# G11_CG_for_G8.net
KiCad netlist of a schematic drawn in EAGLE
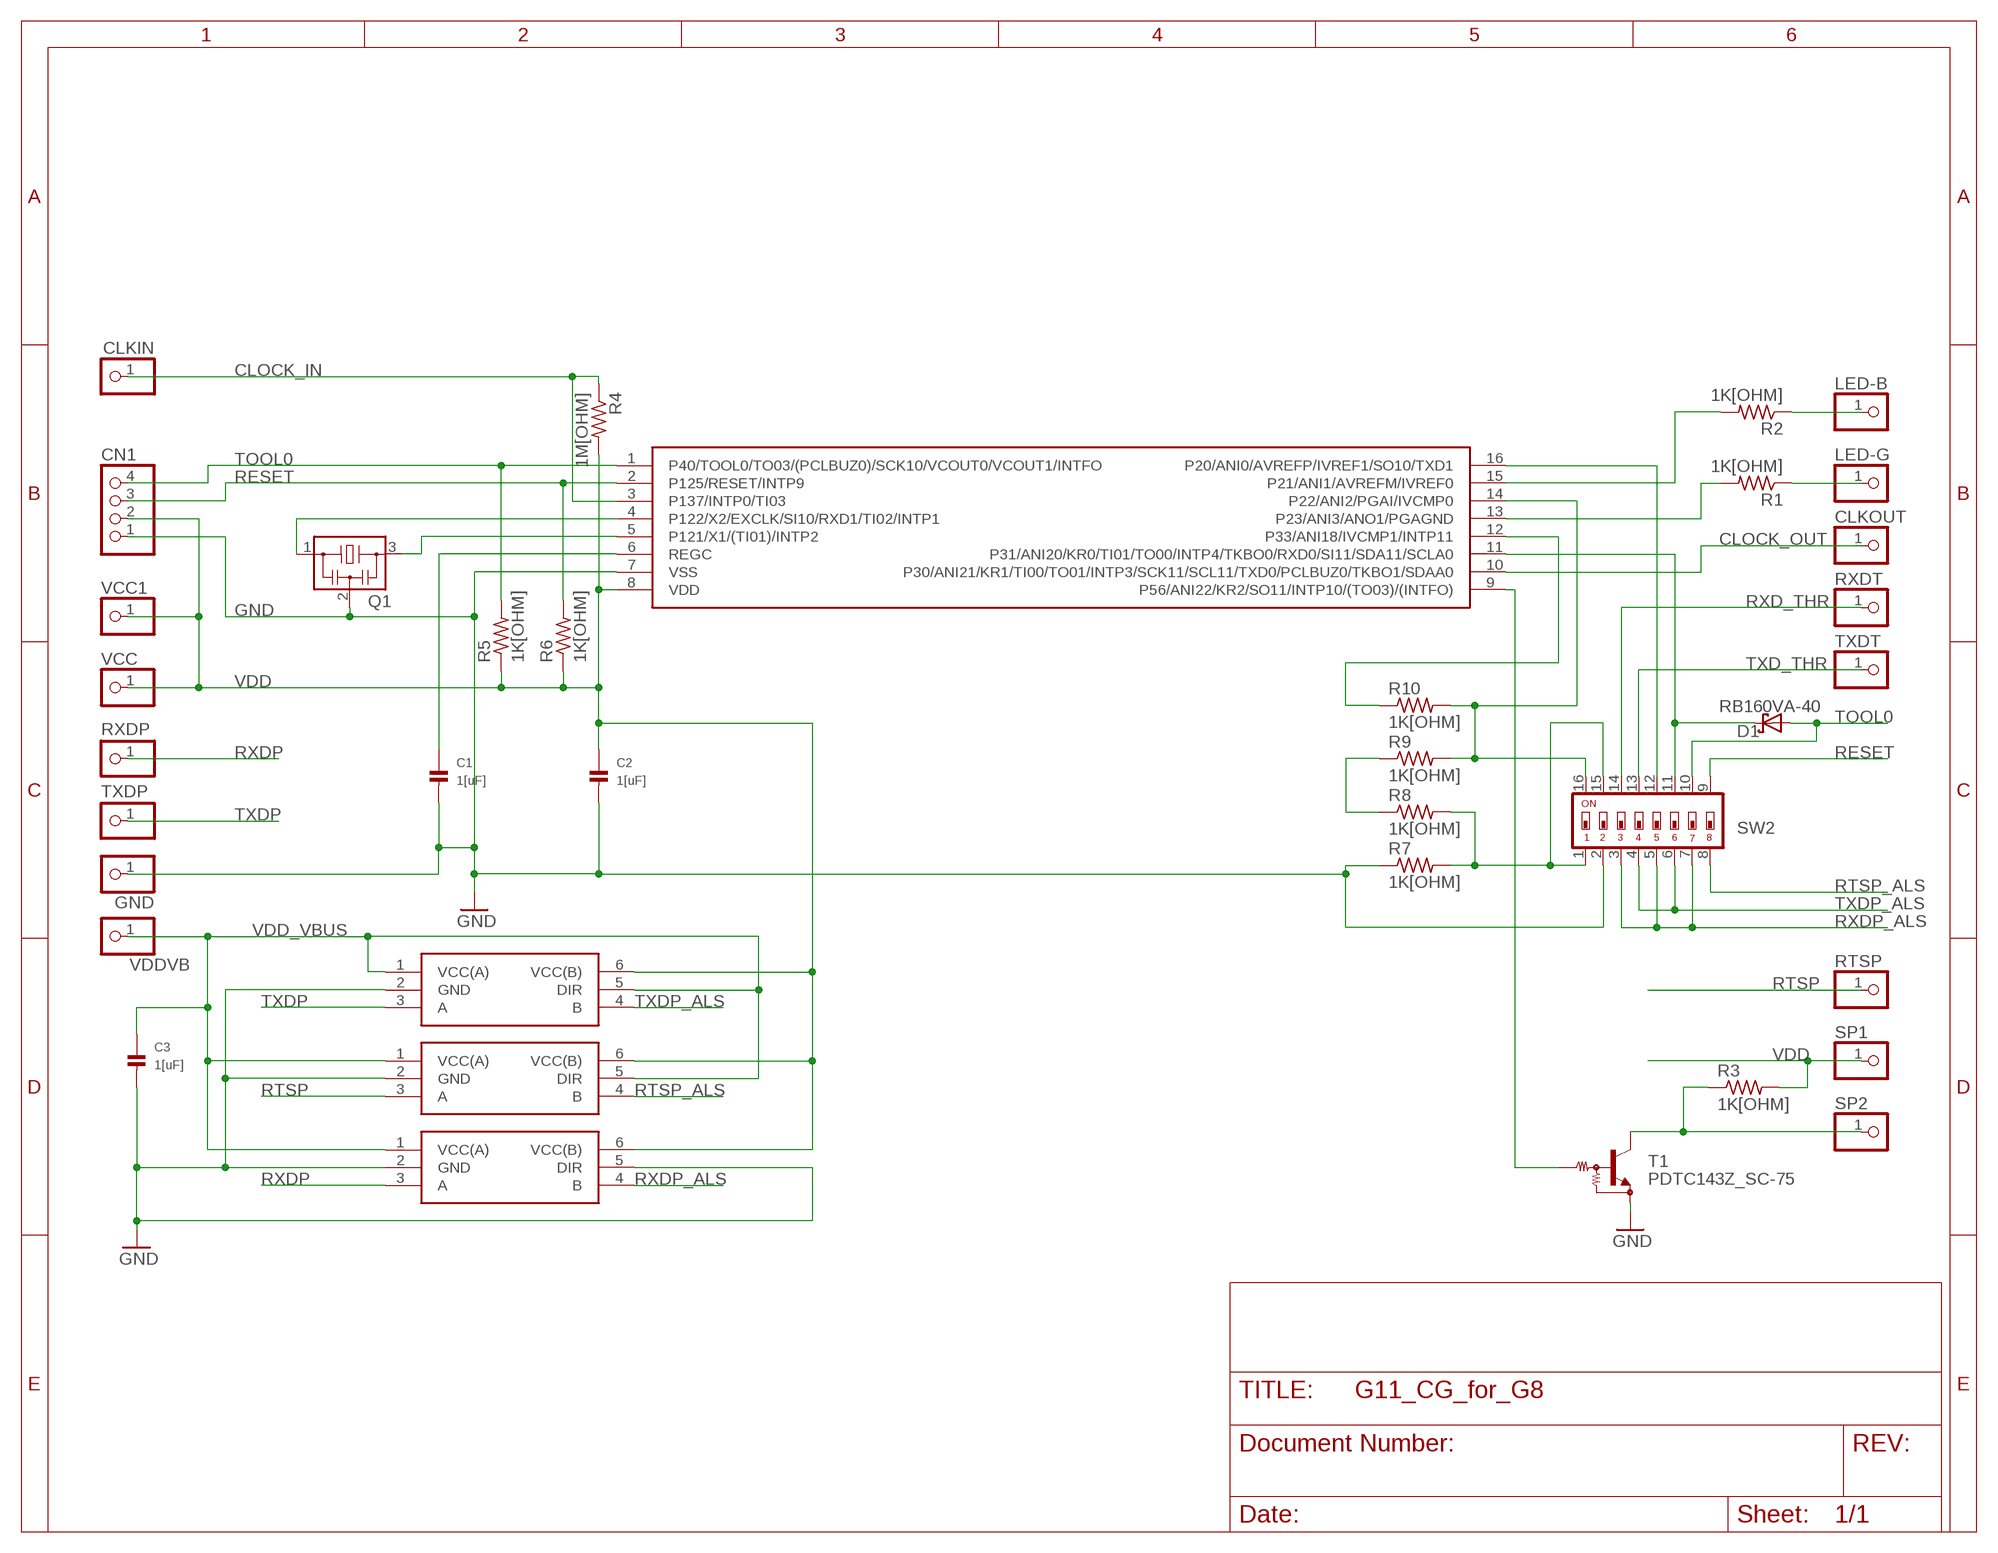
[diagram p0: schematic, sheet 1]

(export (version "E")
  (design (tool "Eeschema 10.0.6"))
  (components
    (comp (ref "C1")
      (value "1[uF]")
      (footprint "eagle-import:_0603")
      (libsource (lib "eagle-import") (part "CAP_CERAMIC_0603"))
    )
    (comp (ref "C2")
      (value "1[uF]")
      (footprint "eagle-import:_0603")
      (libsource (lib "eagle-import") (part "CAP_CERAMIC_0603"))
    )
    (comp (ref "C3")
      (value "1[uF]")
      (footprint "eagle-import:_0603")
      (libsource (lib "eagle-import") (part "CAP_CERAMIC_0603"))
    )
    (comp (ref "CLKIN")
      (value "PINHD-1X1")
      (footprint "eagle-import:1X01")
      (libsource (lib "eagle-import") (part "PINHD-1X1"))
    )
    (comp (ref "CLKOUT")
      (value "PINHD-1X1")
      (footprint "eagle-import:1X01")
      (libsource (lib "eagle-import") (part "PINHD-1X1"))
    )
    (comp (ref "CN1")
      (value "PINHD-1X4")
      (footprint "eagle-import:1X04")
      (libsource (lib "eagle-import") (part "PINHD-1X4"))
    )
    (comp (ref "D1")
      (value "RB160VA-40")
      (footprint "eagle-import:TUMD2")
      (libsource (lib "eagle-import") (part "RB160VA-40"))
    )
    (comp (ref "GND")
      (value "PINHD-1X1")
      (footprint "eagle-import:1X01")
      (libsource (lib "eagle-import") (part "PINHD-1X1"))
    )
    (comp (ref "LED-B")
      (value "PINHD-1X1")
      (footprint "eagle-import:1X01")
      (libsource (lib "eagle-import") (part "PINHD-1X1"))
    )
    (comp (ref "LED-G")
      (value "PINHD-1X1")
      (footprint "eagle-import:1X01")
      (libsource (lib "eagle-import") (part "PINHD-1X1"))
    )
    (comp (ref "Q1")
      (value "CSTNE")
      (footprint "eagle-import:CSTNE")
      (libsource (lib "eagle-import") (part "CSTNE"))
    )
    (comp (ref "R1")
      (value "1K[OHM]")
      (footprint "eagle-import:R0603")
      (libsource (lib "eagle-import") (part "R-US_R0603"))
    )
    (comp (ref "R2")
      (value "1K[OHM]")
      (footprint "eagle-import:R0603")
      (libsource (lib "eagle-import") (part "R-US_R0603"))
    )
    (comp (ref "R3")
      (value "1K[OHM]")
      (footprint "eagle-import:R0603")
      (libsource (lib "eagle-import") (part "R-US_R0603"))
    )
    (comp (ref "R4")
      (value "1M[OHM]")
      (footprint "eagle-import:R0603")
      (libsource (lib "eagle-import") (part "R-US_R0603"))
    )
    (comp (ref "R5")
      (value "1K[OHM]")
      (footprint "eagle-import:R0603")
      (libsource (lib "eagle-import") (part "R-US_R0603"))
    )
    (comp (ref "R6")
      (value "1K[OHM]")
      (footprint "eagle-import:R0603")
      (libsource (lib "eagle-import") (part "R-US_R0603"))
    )
    (comp (ref "R7")
      (value "1K[OHM]")
      (footprint "eagle-import:R0603")
      (libsource (lib "eagle-import") (part "R-US_R0603"))
    )
    (comp (ref "R8")
      (value "1K[OHM]")
      (footprint "eagle-import:R0603")
      (libsource (lib "eagle-import") (part "R-US_R0603"))
    )
    (comp (ref "R9")
      (value "1K[OHM]")
      (footprint "eagle-import:R0603")
      (libsource (lib "eagle-import") (part "R-US_R0603"))
    )
    (comp (ref "R10")
      (value "1K[OHM]")
      (footprint "eagle-import:R0603")
      (libsource (lib "eagle-import") (part "R-US_R0603"))
    )
    (comp (ref "RTSP")
      (value "PINHD-1X1")
      (footprint "eagle-import:1X01")
      (libsource (lib "eagle-import") (part "PINHD-1X1"))
    )
    (comp (ref "RXDP")
      (value "PINHD-1X1")
      (footprint "eagle-import:1X01")
      (libsource (lib "eagle-import") (part "PINHD-1X1"))
    )
    (comp (ref "RXDT")
      (value "PINHD-1X1")
      (footprint "eagle-import:1X01")
      (libsource (lib "eagle-import") (part "PINHD-1X1"))
    )
    (comp (ref "SP1")
      (value "PINHD-1X1")
      (footprint "eagle-import:1X01")
      (libsource (lib "eagle-import") (part "PINHD-1X1"))
    )
    (comp (ref "SP2")
      (value "PINHD-1X1")
      (footprint "eagle-import:1X01")
      (libsource (lib "eagle-import") (part "PINHD-1X1"))
    )
    (comp (ref "SW2")
      (value "SWS008")
      (footprint "eagle-import:SMS-008")
      (libsource (lib "eagle-import") (part "SWS008"))
    )
    (comp (ref "T1")
      (value "PDTC143Z_SC-75")
      (footprint "eagle-import:SC-75")
      (libsource (lib "eagle-import") (part "DTC1XXXZPDTC143Z"))
    )
    (comp (ref "TXDP")
      (value "PINHD-1X1")
      (footprint "eagle-import:1X01")
      (libsource (lib "eagle-import") (part "PINHD-1X1"))
    )
    (comp (ref "TXDT")
      (value "PINHD-1X1")
      (footprint "eagle-import:1X01")
      (libsource (lib "eagle-import") (part "PINHD-1X1"))
    )
    (comp (ref "U1")
      (value "RL78/G11_SSOP16")
      (footprint "eagle-import:SSOP16_(4.4X5.0)")
      (libsource (lib "eagle-import") (part "RL78/G11_SSOP16"))
    )
    (comp (ref "U2")
      (value "74LVC1T45W6")
      (footprint "eagle-import:SOT-26")
      (libsource (lib "eagle-import") (part "74LVC1T45W6"))
    )
    (comp (ref "U3")
      (value "74LVC1T45W6")
      (footprint "eagle-import:SOT-26")
      (libsource (lib "eagle-import") (part "74LVC1T45W6"))
    )
    (comp (ref "U4")
      (value "74LVC1T45W6")
      (footprint "eagle-import:SOT-26")
      (libsource (lib "eagle-import") (part "74LVC1T45W6"))
    )
    (comp (ref "VCC")
      (value "PINHD-1X1")
      (footprint "eagle-import:1X01")
      (libsource (lib "eagle-import") (part "PINHD-1X1"))
    )
    (comp (ref "VCC1")
      (value "PINHD-1X1")
      (footprint "eagle-import:1X01")
      (libsource (lib "eagle-import") (part "PINHD-1X1"))
    )
    (comp (ref "VDDVB")
      (value "PINHD-1X1")
      (footprint "eagle-import:1X01")
      (libsource (lib "eagle-import") (part "PINHD-1X1"))
    )
  )
  (nets
    (net (code "1") (name "/CLOCK_IN") (class "Default")
      (node (ref "CLKIN") (pin "1") (pinfunction "1_1") (pintype "passive"))
      (node (ref "R4") (pin "1") (pinfunction "1_1") (pintype "passive"))
      (node (ref "U1") (pin "3") (pinfunction "P137/INTP0/TI03_3") (pintype "bidirectional"))
    )
    (net (code "2") (name "/CLOCK_OUT") (class "Default")
      (node (ref "CLKOUT") (pin "1") (pinfunction "1_1") (pintype "passive"))
      (node (ref "U1") (pin "10") (pinfunction "P30/ANI21/KR1/TI00/TO01/INTP3/SCK11/SCL11/TXD0/PCLBUZ0/TKBO1/SDAA0_10") (pintype "bidirectional"))
    )
    (net (code "3") (name "/RESET") (class "Default")
      (node (ref "CN1") (pin "3") (pinfunction "3_3") (pintype "passive"))
      (node (ref "R6") (pin "2") (pinfunction "2_2") (pintype "passive"))
      (node (ref "SW2") (pin "9") (pinfunction "9_9") (pintype "passive"))
      (node (ref "U1") (pin "2") (pinfunction "P125/RESET/INTP9_2") (pintype "bidirectional"))
    )
    (net (code "4") (name "/RTSP") (class "Default")
      (node (ref "RTSP") (pin "1") (pinfunction "1_1") (pintype "passive"))
      (node (ref "U3") (pin "3") (pinfunction "A_3") (pintype "bidirectional"))
    )
    (net (code "5") (name "/RTSP_ALS") (class "Default")
      (node (ref "SW2") (pin "8") (pinfunction "8_8") (pintype "passive"))
      (node (ref "U3") (pin "4") (pinfunction "B_4") (pintype "bidirectional"))
    )
    (net (code "6") (name "/RXDP") (class "Default")
      (node (ref "RXDP") (pin "1") (pinfunction "1_1") (pintype "passive"))
      (node (ref "U4") (pin "3") (pinfunction "A_3") (pintype "bidirectional"))
    )
    (net (code "7") (name "/RXDP_ALS") (class "Default")
      (node (ref "SW2") (pin "3") (pinfunction "3_3") (pintype "passive"))
      (node (ref "SW2") (pin "5") (pinfunction "5_5") (pintype "passive"))
      (node (ref "SW2") (pin "7") (pinfunction "7_7") (pintype "passive"))
      (node (ref "U4") (pin "4") (pinfunction "B_4") (pintype "bidirectional"))
    )
    (net (code "8") (name "/RXD_THR") (class "Default")
      (node (ref "RXDT") (pin "1") (pinfunction "1_1") (pintype "passive"))
      (node (ref "SW2") (pin "14") (pinfunction "14_14") (pintype "passive"))
    )
    (net (code "9") (name "/TOOL0") (class "Default")
      (node (ref "CN1") (pin "4") (pinfunction "4_4") (pintype "passive"))
      (node (ref "D1") (pin "P$2") (pinfunction "A_P$2") (pintype "passive"))
      (node (ref "R5") (pin "2") (pinfunction "2_2") (pintype "passive"))
      (node (ref "SW2") (pin "10") (pinfunction "10_10") (pintype "passive"))
      (node (ref "U1") (pin "1") (pinfunction "P40/TOOL0/TO03/(PCLBUZ0)/SCK10/VCOUT0/VCOUT1/INTFO_1") (pintype "bidirectional"))
    )
    (net (code "10") (name "/TXDP") (class "Default")
      (node (ref "TXDP") (pin "1") (pinfunction "1_1") (pintype "passive"))
      (node (ref "U2") (pin "3") (pinfunction "A_3") (pintype "bidirectional"))
    )
    (net (code "11") (name "/TXDP_ALS") (class "Default")
      (node (ref "SW2") (pin "4") (pinfunction "4_4") (pintype "passive"))
      (node (ref "SW2") (pin "6") (pinfunction "6_6") (pintype "passive"))
      (node (ref "U2") (pin "4") (pinfunction "B_4") (pintype "bidirectional"))
    )
    (net (code "12") (name "/TXD_THR") (class "Default")
      (node (ref "SW2") (pin "13") (pinfunction "13_13") (pintype "passive"))
      (node (ref "TXDT") (pin "1") (pinfunction "1_1") (pintype "passive"))
    )
    (net (code "13") (name "/VDD") (class "Default")
      (node (ref "C2") (pin "1") (pinfunction "P$1_1") (pintype "passive"))
      (node (ref "CN1") (pin "2") (pinfunction "2_2") (pintype "passive"))
      (node (ref "R3") (pin "2") (pinfunction "2_2") (pintype "passive"))
      (node (ref "R4") (pin "2") (pinfunction "2_2") (pintype "passive"))
      (node (ref "R5") (pin "1") (pinfunction "1_1") (pintype "passive"))
      (node (ref "R6") (pin "1") (pinfunction "1_1") (pintype "passive"))
      (node (ref "SP1") (pin "1") (pinfunction "1_1") (pintype "passive"))
      (node (ref "U1") (pin "8") (pinfunction "VDD_8") (pintype "power_in"))
      (node (ref "U2") (pin "6") (pinfunction "VCC(B)_6") (pintype "power_in"))
      (node (ref "U3") (pin "6") (pinfunction "VCC(B)_6") (pintype "power_in"))
      (node (ref "U4") (pin "6") (pinfunction "VCC(B)_6") (pintype "power_in"))
      (node (ref "VCC") (pin "1") (pinfunction "1_1") (pintype "passive"))
      (node (ref "VCC1") (pin "1") (pinfunction "1_1") (pintype "passive"))
    )
    (net (code "14") (name "/VDD_VBUS") (class "Default")
      (node (ref "C3") (pin "1") (pinfunction "P$1_1") (pintype "passive"))
      (node (ref "U2") (pin "1") (pinfunction "VCC(A)_1") (pintype "power_in"))
      (node (ref "U2") (pin "5") (pinfunction "DIR_5") (pintype "input"))
      (node (ref "U3") (pin "1") (pinfunction "VCC(A)_1") (pintype "power_in"))
      (node (ref "U3") (pin "5") (pinfunction "DIR_5") (pintype "input"))
      (node (ref "U4") (pin "1") (pinfunction "VCC(A)_1") (pintype "power_in"))
      (node (ref "VDDVB") (pin "1") (pinfunction "1_1") (pintype "passive"))
    )
    (net (code "15") (name "GND") (class "Default")
      (node (ref "C1") (pin "2") (pinfunction "P$2_2") (pintype "passive"))
      (node (ref "C2") (pin "2") (pinfunction "P$2_2") (pintype "passive"))
      (node (ref "C3") (pin "2") (pinfunction "P$2_2") (pintype "passive"))
      (node (ref "CN1") (pin "1") (pinfunction "1_1") (pintype "passive"))
      (node (ref "GND") (pin "1") (pinfunction "1_1") (pintype "passive"))
      (node (ref "Q1") (pin "2") (pinfunction "2_2") (pintype "passive"))
      (node (ref "R7") (pin "1") (pinfunction "1_1") (pintype "passive"))
      (node (ref "SW2") (pin "2") (pinfunction "2_2") (pintype "passive"))
      (node (ref "T1") (pin "2") (pinfunction "E_2") (pintype "passive"))
      (node (ref "U1") (pin "7") (pinfunction "VSS_7") (pintype "power_in"))
      (node (ref "U2") (pin "2") (pinfunction "GND_2") (pintype "power_in"))
      (node (ref "U3") (pin "2") (pinfunction "GND_2") (pintype "power_in"))
      (node (ref "U4") (pin "2") (pinfunction "GND_2") (pintype "power_in"))
      (node (ref "U4") (pin "5") (pinfunction "DIR_5") (pintype "input"))
    )
    (net (code "16") (name "Net-(C1-P$1)") (class "Default")
      (node (ref "C1") (pin "1") (pinfunction "P$1_1") (pintype "passive"))
      (node (ref "U1") (pin "6") (pinfunction "REGC_6") (pintype "bidirectional"))
    )
    (net (code "17") (name "Net-(D1-C)") (class "Default")
      (node (ref "D1") (pin "P$1") (pinfunction "C_P$1") (pintype "passive"))
      (node (ref "SW2") (pin "11") (pinfunction "11_11") (pintype "passive"))
      (node (ref "U1") (pin "11") (pinfunction "P31/ANI20/KR0/TI01/TO00/INTP4/TKBO0/RXD0/SI11/SDA11/SCLA0_11") (pintype "bidirectional"))
    )
    (net (code "18") (name "Net-(LED-B-Pad1)") (class "Default")
      (node (ref "LED-B") (pin "1") (pinfunction "1_1") (pintype "passive"))
      (node (ref "R2") (pin "1") (pinfunction "1_1") (pintype "passive"))
    )
    (net (code "19") (name "Net-(LED-G-Pad1)") (class "Default")
      (node (ref "LED-G") (pin "1") (pinfunction "1_1") (pintype "passive"))
      (node (ref "R1") (pin "1") (pinfunction "1_1") (pintype "passive"))
    )
    (net (code "20") (name "Net-(R7-Pad2)") (class "Default")
      (node (ref "R7") (pin "2") (pinfunction "2_2") (pintype "passive"))
      (node (ref "R8") (pin "2") (pinfunction "2_2") (pintype "passive"))
      (node (ref "SW2") (pin "1") (pinfunction "1_1") (pintype "passive"))
      (node (ref "SW2") (pin "15") (pinfunction "15_15") (pintype "passive"))
    )
    (net (code "21") (name "Net-(R8-Pad1)") (class "Default")
      (node (ref "R8") (pin "1") (pinfunction "1_1") (pintype "passive"))
      (node (ref "R9") (pin "1") (pinfunction "1_1") (pintype "passive"))
    )
    (net (code "22") (name "Net-(T1-B)") (class "Default")
      (node (ref "T1") (pin "1") (pinfunction "B_1") (pintype "passive"))
      (node (ref "U1") (pin "9") (pinfunction "P56/ANI22/KR2/SO11/INTP10/(TO03)/(INTFO)_9") (pintype "bidirectional"))
    )
    (net (code "23") (name "Net-(T1-C)") (class "Default")
      (node (ref "R3") (pin "1") (pinfunction "1_1") (pintype "passive"))
      (node (ref "SP2") (pin "1") (pinfunction "1_1") (pintype "passive"))
      (node (ref "T1") (pin "3") (pinfunction "C_3") (pintype "passive"))
    )
    (net (code "24") (name "Net-(U1-P20{slash}ANI0{slash}AVREFP{slash}IVREF1{slash}SO10{slash}TXD1)") (class "Default")
      (node (ref "SW2") (pin "12") (pinfunction "12_12") (pintype "passive"))
      (node (ref "U1") (pin "16") (pinfunction "P20/ANI0/AVREFP/IVREF1/SO10/TXD1_16") (pintype "bidirectional"))
    )
    (net (code "25") (name "Net-(U1-P21{slash}ANI1{slash}AVREFM{slash}IVREF0)") (class "Default")
      (node (ref "R2") (pin "2") (pinfunction "2_2") (pintype "passive"))
      (node (ref "U1") (pin "15") (pinfunction "P21/ANI1/AVREFM/IVREF0_15") (pintype "bidirectional"))
    )
    (net (code "26") (name "Net-(U1-P22{slash}ANI2{slash}PGAI{slash}IVCMP0)") (class "Default")
      (node (ref "R10") (pin "2") (pinfunction "2_2") (pintype "passive"))
      (node (ref "R9") (pin "2") (pinfunction "2_2") (pintype "passive"))
      (node (ref "SW2") (pin "16") (pinfunction "16_16") (pintype "passive"))
      (node (ref "U1") (pin "14") (pinfunction "P22/ANI2/PGAI/IVCMP0_14") (pintype "bidirectional"))
    )
    (net (code "27") (name "Net-(U1-P23{slash}ANI3{slash}ANO1{slash}PGAGND)") (class "Default")
      (node (ref "R1") (pin "2") (pinfunction "2_2") (pintype "passive"))
      (node (ref "U1") (pin "13") (pinfunction "P23/ANI3/ANO1/PGAGND_13") (pintype "bidirectional"))
    )
    (net (code "28") (name "Net-(U1-P33{slash}ANI18{slash}IVCMP1{slash}INTP11)") (class "Default")
      (node (ref "R10") (pin "1") (pinfunction "1_1") (pintype "passive"))
      (node (ref "U1") (pin "12") (pinfunction "P33/ANI18/IVCMP1/INTP11_12") (pintype "bidirectional"))
    )
    (net (code "29") (name "Net-(U1-P121{slash}X1{slash}(TI01){slash}INTP2)") (class "Default")
      (node (ref "Q1") (pin "3") (pinfunction "3_3") (pintype "passive"))
      (node (ref "U1") (pin "5") (pinfunction "P121/X1/(TI01)/INTP2_5") (pintype "bidirectional"))
    )
    (net (code "30") (name "Net-(U1-P122{slash}X2{slash}EXCLK{slash}SI10{slash}RXD1{slash}TI02{slash}INTP1)") (class "Default")
      (node (ref "Q1") (pin "1") (pinfunction "1_1") (pintype "passive"))
      (node (ref "U1") (pin "4") (pinfunction "P122/X2/EXCLK/SI10/RXD1/TI02/INTP1_4") (pintype "bidirectional"))
    )
  )
)
